# Display.net
KiCad netlist of a schematic drawn in Altium Designer
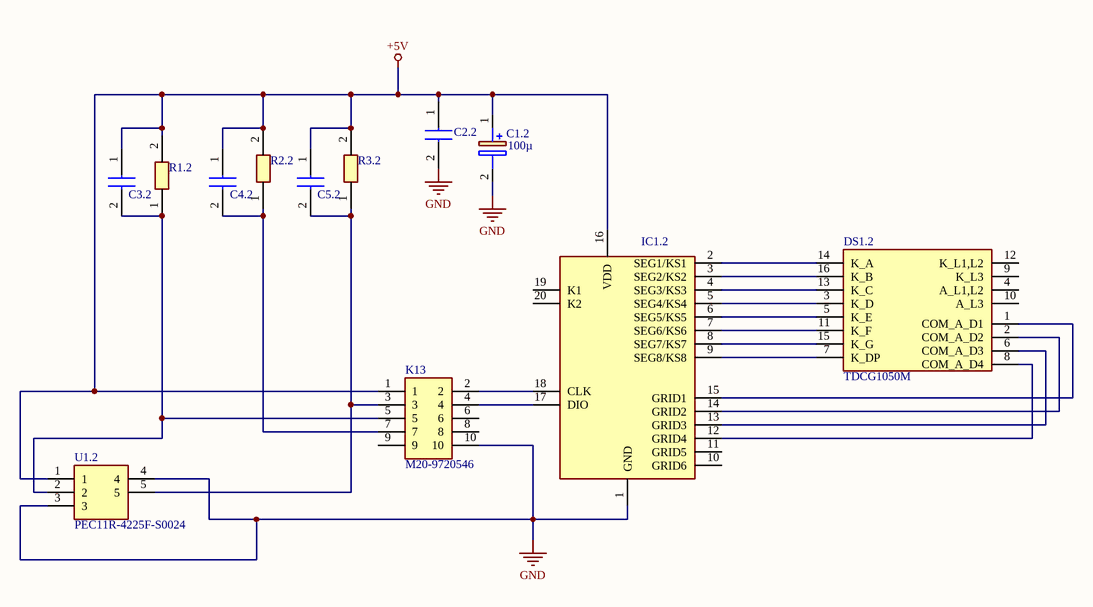
[diagram p0: Display.SchDoc]

(export (version "E")
  (design (tool "Eeschema 10.0.6"))
  (components
    (comp (ref "C1.2")
      (value "100µ")
      (footprint "SamacSys:CAPPRD200W52D500H1250")
      (description "Capacitor Polarised")
      (fields
        (field (name "MANUFACTURER_PART_NUMBER") "860010672009")
        (field (name "MOUSER PART NUMBER") "710-860010672009")
      )
      (libsource (lib "SoldeerBoutLib") (part "860010672009"))
    )
    (comp (ref "C2.2")
      (value "860010674014")
      (footprint "SamacSys:CAPPRD350W52D800H1300")
      (description "Capacitor")
      (fields (field (name "MOUSER PART NUMBER") "710-860010674014"))
      (libsource (lib "SoldeerBoutLib") (part "860010674014"))
    )
    (comp (ref "C3.2")
      (value "860010674014")
      (footprint "SamacSys:CAPPRD350W52D800H1300")
      (description "Capacitor")
      (fields (field (name "MOUSER PART NUMBER") "710-860010674014"))
      (libsource (lib "SoldeerBoutLib") (part "860010674014"))
    )
    (comp (ref "C4.2")
      (value "860010674014")
      (footprint "SamacSys:CAPPRD350W52D800H1300")
      (description "Capacitor")
      (fields (field (name "MOUSER PART NUMBER") "710-860010674014"))
      (libsource (lib "SoldeerBoutLib") (part "860010674014"))
    )
    (comp (ref "C5.2")
      (value "860010674014")
      (footprint "SamacSys:CAPPRD350W52D800H1300")
      (description "Capacitor")
      (fields (field (name "MOUSER PART NUMBER") "710-860010674014"))
      (libsource (lib "SoldeerBoutLib") (part "860010674014"))
    )
    (comp (ref "DS1.2")
      (value "TDCG1050M")
      (footprint "SamacSys:DIPS1016W75P254L4020H725Q16N")
      (description "Display")
      (fields (field (name "MOUSER PART NUMBER") "78-TDCG1050"))
      (libsource (lib "SoldeerBoutLib") (part "TDCG1050M"))
    )
    (comp (ref "IC1.2")
      (value "TM1637__SOP_")
      (footprint "SamacSys:SOIC127P1045X280-20N")
      (description "Integrated Circuit")
      (fields (field (name "MANUFACTURER_PART_NUMBER") "TM1637 (SOP)"))
      (libsource (lib "SoldeerBoutLib") (part "TM1637__SOP_"))
    )
    (comp (ref "K13")
      (value "M20-9720546")
      (footprint "SamacSys:HDRV10W64P254_2X5_1270X508X954P")
      (description "Connector")
      (libsource (lib "SoldeerBoutLib") (part "M20-9720546"))
    )
    (comp (ref "R1.2")
      (value "~")
      (footprint "SamacSys:RESC2012X90N")
      (description "Resistor")
      (fields (field (name "MANUFACTURER_PART_NUMBER") "CFN0805-JZ-R010ELF"))
      (libsource (lib "SoldeerBoutLib") (part "CFN0805-JZ-R010ELF"))
    )
    (comp (ref "R2.2")
      (value "~")
      (footprint "SamacSys:RESC2012X90N")
      (description "Resistor")
      (fields (field (name "MANUFACTURER_PART_NUMBER") "CFN0805-JZ-R010ELF"))
      (libsource (lib "SoldeerBoutLib") (part "CFN0805-JZ-R010ELF"))
    )
    (comp (ref "R3.2")
      (value "~")
      (footprint "SamacSys:RESC2012X90N")
      (description "Resistor")
      (fields (field (name "MANUFACTURER_PART_NUMBER") "CFN0805-JZ-R010ELF"))
      (libsource (lib "SoldeerBoutLib") (part "CFN0805-JZ-R010ELF"))
    )
    (comp (ref "U1.2")
      (value "PEC11R-4225F-S0024")
      (footprint "SamacSys:PEC12R-4XXXF-SXXXX_1")
      (description "Undefined or Miscellaneous")
      (fields (field (name "MOUSER PART NUMBER") "652-PEC11R-4225F-S24"))
      (libsource (lib "SoldeerBoutLib") (part "PEC11R-4225F-S0024"))
    )
  )
  (nets
    (net (code "1") (name "+5V") (class "Default")
      (node (ref "C1.2") (pin "1") (pinfunction "+_1") (pintype "passive"))
      (node (ref "C2.2") (pin "1") (pinfunction "+_1") (pintype "passive"))
      (node (ref "C3.2") (pin "1") (pinfunction "+_1") (pintype "passive"))
      (node (ref "C4.2") (pin "1") (pinfunction "+_1") (pintype "passive"))
      (node (ref "C5.2") (pin "1") (pinfunction "+_1") (pintype "passive"))
      (node (ref "IC1.2") (pin "16") (pinfunction "VDD_16") (pintype "passive"))
      (node (ref "K13") (pin "1") (pinfunction "1_1") (pintype "passive"))
      (node (ref "R1.2") (pin "2") (pinfunction "2_2") (pintype "passive"))
      (node (ref "R2.2") (pin "2") (pinfunction "2_2") (pintype "passive"))
      (node (ref "R3.2") (pin "2") (pinfunction "2_2") (pintype "passive"))
      (node (ref "U1.2") (pin "1") (pinfunction "1_1") (pintype "passive"))
    )
    (net (code "2") (name "GND") (class "Default")
      (node (ref "C1.2") (pin "2") (pinfunction "-_2") (pintype "passive"))
      (node (ref "C2.2") (pin "2") (pinfunction "-_2") (pintype "passive"))
      (node (ref "IC1.2") (pin "1") (pinfunction "GND_1") (pintype "passive"))
      (node (ref "K13") (pin "10") (pinfunction "10_10") (pintype "passive"))
      (node (ref "U1.2") (pin "3") (pinfunction "3_3") (pintype "passive"))
      (node (ref "U1.2") (pin "4") (pinfunction "4_4") (pintype "passive"))
    )
    (net (code "3") (name "Net-(C3.2--)") (class "Default")
      (node (ref "C3.2") (pin "2") (pinfunction "-_2") (pintype "passive"))
      (node (ref "K13") (pin "5") (pinfunction "5_5") (pintype "passive"))
      (node (ref "R1.2") (pin "1") (pinfunction "1_1") (pintype "passive"))
      (node (ref "U1.2") (pin "2") (pinfunction "2_2") (pintype "passive"))
    )
    (net (code "4") (name "Net-(C4.2--)") (class "Default")
      (node (ref "C4.2") (pin "2") (pinfunction "-_2") (pintype "passive"))
      (node (ref "K13") (pin "7") (pinfunction "7_7") (pintype "passive"))
      (node (ref "R2.2") (pin "1") (pinfunction "1_1") (pintype "passive"))
    )
    (net (code "5") (name "Net-(C5.2--)") (class "Default")
      (node (ref "C5.2") (pin "2") (pinfunction "-_2") (pintype "passive"))
      (node (ref "K13") (pin "3") (pinfunction "3_3") (pintype "passive"))
      (node (ref "R3.2") (pin "1") (pinfunction "1_1") (pintype "passive"))
      (node (ref "U1.2") (pin "5") (pinfunction "5_5") (pintype "passive"))
    )
    (net (code "6") (name "Net-(DS1.2-COM_A_D1)") (class "Default")
      (node (ref "DS1.2") (pin "1") (pinfunction "COM_A_D1_1") (pintype "passive"))
      (node (ref "IC1.2") (pin "15") (pinfunction "GRID1_15") (pintype "passive"))
    )
    (net (code "7") (name "Net-(DS1.2-COM_A_D2)") (class "Default")
      (node (ref "DS1.2") (pin "2") (pinfunction "COM_A_D2_2") (pintype "passive"))
      (node (ref "IC1.2") (pin "14") (pinfunction "GRID2_14") (pintype "passive"))
    )
    (net (code "8") (name "Net-(DS1.2-COM_A_D3)") (class "Default")
      (node (ref "DS1.2") (pin "6") (pinfunction "COM_A_D3_6") (pintype "passive"))
      (node (ref "IC1.2") (pin "13") (pinfunction "GRID3_13") (pintype "passive"))
    )
    (net (code "9") (name "Net-(DS1.2-COM_A_D4)") (class "Default")
      (node (ref "DS1.2") (pin "8") (pinfunction "COM_A_D4_8") (pintype "passive"))
      (node (ref "IC1.2") (pin "12") (pinfunction "GRID4_12") (pintype "passive"))
    )
    (net (code "10") (name "Net-(DS1.2-K_A)") (class "Default")
      (node (ref "DS1.2") (pin "14") (pinfunction "K_A_14") (pintype "passive"))
      (node (ref "IC1.2") (pin "2") (pinfunction "SEG1/KS1_2") (pintype "passive"))
    )
    (net (code "11") (name "Net-(DS1.2-K_B)") (class "Default")
      (node (ref "DS1.2") (pin "16") (pinfunction "K_B_16") (pintype "passive"))
      (node (ref "IC1.2") (pin "3") (pinfunction "SEG2/KS2_3") (pintype "passive"))
    )
    (net (code "12") (name "Net-(DS1.2-K_C)") (class "Default")
      (node (ref "DS1.2") (pin "13") (pinfunction "K_C_13") (pintype "passive"))
      (node (ref "IC1.2") (pin "4") (pinfunction "SEG3/KS3_4") (pintype "passive"))
    )
    (net (code "13") (name "Net-(DS1.2-K_D)") (class "Default")
      (node (ref "DS1.2") (pin "3") (pinfunction "K_D_3") (pintype "passive"))
      (node (ref "IC1.2") (pin "5") (pinfunction "SEG4/KS4_5") (pintype "passive"))
    )
    (net (code "14") (name "Net-(DS1.2-K_DP)") (class "Default")
      (node (ref "DS1.2") (pin "7") (pinfunction "K_DP_7") (pintype "passive"))
      (node (ref "IC1.2") (pin "9") (pinfunction "SEG8/KS8_9") (pintype "passive"))
    )
    (net (code "15") (name "Net-(DS1.2-K_E)") (class "Default")
      (node (ref "DS1.2") (pin "5") (pinfunction "K_E_5") (pintype "passive"))
      (node (ref "IC1.2") (pin "6") (pinfunction "SEG5/KS5_6") (pintype "passive"))
    )
    (net (code "16") (name "Net-(DS1.2-K_F)") (class "Default")
      (node (ref "DS1.2") (pin "11") (pinfunction "K_F_11") (pintype "passive"))
      (node (ref "IC1.2") (pin "7") (pinfunction "SEG6/KS6_7") (pintype "passive"))
    )
    (net (code "17") (name "Net-(DS1.2-K_G)") (class "Default")
      (node (ref "DS1.2") (pin "15") (pinfunction "K_G_15") (pintype "passive"))
      (node (ref "IC1.2") (pin "8") (pinfunction "SEG7/KS7_8") (pintype "passive"))
    )
    (net (code "18") (name "Net-(IC1.2-CLK)") (class "Default")
      (node (ref "IC1.2") (pin "18") (pinfunction "CLK_18") (pintype "passive"))
      (node (ref "K13") (pin "2") (pinfunction "2_2") (pintype "passive"))
    )
    (net (code "19") (name "Net-(IC1.2-DIO)") (class "Default")
      (node (ref "IC1.2") (pin "17") (pinfunction "DIO_17") (pintype "passive"))
      (node (ref "K13") (pin "4") (pinfunction "4_4") (pintype "passive"))
    )
    (net (code "20") (name "unconnected-(DS1.2-A_L1,L2-Pad4)") (class "Default")
      (node (ref "DS1.2") (pin "4") (pinfunction "A_L1,L2_4") (pintype "passive"))
    )
    (net (code "21") (name "unconnected-(DS1.2-A_L3-Pad10)") (class "Default")
      (node (ref "DS1.2") (pin "10") (pinfunction "A_L3_10") (pintype "passive"))
    )
    (net (code "22") (name "unconnected-(DS1.2-K_L1,L2-Pad12)") (class "Default")
      (node (ref "DS1.2") (pin "12") (pinfunction "K_L1,L2_12") (pintype "passive"))
    )
    (net (code "23") (name "unconnected-(DS1.2-K_L3-Pad9)") (class "Default")
      (node (ref "DS1.2") (pin "9") (pinfunction "K_L3_9") (pintype "passive"))
    )
    (net (code "24") (name "unconnected-(IC1.2-GRID5-Pad11)") (class "Default")
      (node (ref "IC1.2") (pin "11") (pinfunction "GRID5_11") (pintype "passive"))
    )
    (net (code "25") (name "unconnected-(IC1.2-GRID6-Pad10)") (class "Default")
      (node (ref "IC1.2") (pin "10") (pinfunction "GRID6_10") (pintype "passive"))
    )
    (net (code "26") (name "unconnected-(IC1.2-K1-Pad19)") (class "Default")
      (node (ref "IC1.2") (pin "19") (pinfunction "K1_19") (pintype "passive"))
    )
    (net (code "27") (name "unconnected-(IC1.2-K2-Pad20)") (class "Default")
      (node (ref "IC1.2") (pin "20") (pinfunction "K2_20") (pintype "passive"))
    )
    (net (code "28") (name "unconnected-(K13-Pad6)") (class "Default")
      (node (ref "K13") (pin "6") (pinfunction "6_6") (pintype "passive"))
    )
    (net (code "29") (name "unconnected-(K13-Pad8)") (class "Default")
      (node (ref "K13") (pin "8") (pinfunction "8_8") (pintype "passive"))
    )
    (net (code "30") (name "unconnected-(K13-Pad9)") (class "Default")
      (node (ref "K13") (pin "9") (pinfunction "9_9") (pintype "passive"))
    )
  )
)
